# PowerSwitch_P12V.net
KiCad netlist of a schematic drawn in Altium Designer
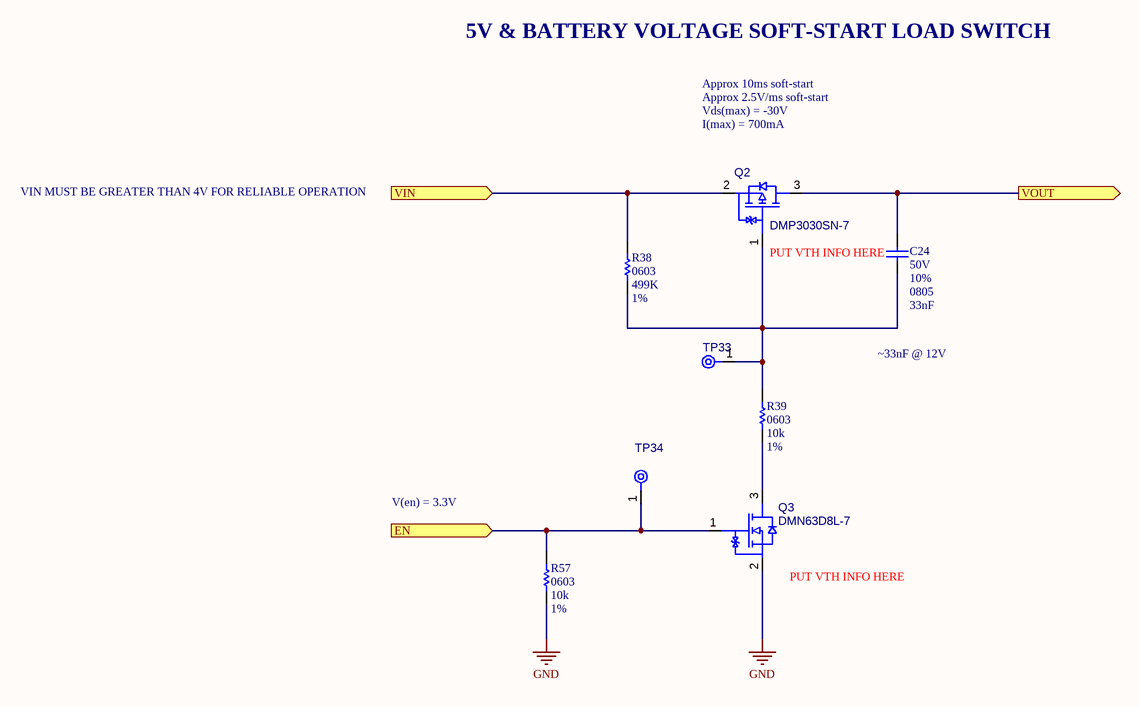
[diagram p0: PowerSwitch_P12V.SchDoc]

(export (version "E")
  (design (tool "Eeschema 10.0.6"))
  (components
    (comp (ref "C24")
      (value "33nF")
      (footprint "CAPC2013X95X50ML10T25")
      (description "Chip Capacitor, 33nF, 10%, 50 V, X7R 0805 (2012 Metric)")
      (fields
        (field (name "VOLTAGE RATING") "50V")
        (field (name "TOLERANCE") "10%")
        (field (name "CASE/PACKAGE") "0805")
        (field (name "Comment") "Capacitor 33nF 10%, 50V, X7R, 0805")
      )
      (libsource (lib "Applied Physics Lab") (part "CAP-NP-2"))
    )
    (comp (ref "Q2")
      (value "DMP3030SN-7")
      (footprint "SOT95P164X140-3M")
      (description "Trans Mosfet P-ch 30V 0.7A 3-PIN SC-59 T/r / Mosfet P-ch 30V 700MA SC59-3")
      (libsource (lib "Applied Physics Lab") (part "CMP-00006-6"))
    )
    (comp (ref "Q3")
      (value "DMN63D8L-7")
      (footprint "SOT95P240X110-3M")
      (description "Trans Mosfet N-ch 30V 0.35A 3-PIN SOT-23 T/r")
      (libsource (lib "Applied Physics Lab") (part "CMP-00005-6"))
    )
    (comp (ref "R38")
      (value "499K")
      (footprint "RESC1609X50X30ML08T20")
      (description "Chip Resistor, 499k Ohm, +/- 1%, 0.1 W, -55 to 155 degC, 0603 (1608 Metric)")
      (fields
        (field (name "POWER") "100mW")
        (field (name "CASE/PACKAGE") "0603")
        (field (name "TOLERANCE") "1%")
        (field (name "Comment") "Resistor 499K +/-1% 0603 100 mW")
      )
      (libsource (lib "Applied Physics Lab") (part "RES-2"))
    )
    (comp (ref "R39")
      (value "10k")
      (footprint "RESC1608X55X25ML10T15")
      (description "Chip Resistor, 10 KOhm, +/- 1%, 01 W, -55 to 155 degC, 0603 (1608 Metric)")
      (fields
        (field (name "POWER") "100mW")
        (field (name "CASE/PACKAGE") "0603")
        (field (name "TOLERANCE") "1%")
        (field (name "Comment") "Resistor 10k +/-1% 0603 100 mW")
      )
      (libsource (lib "Applied Physics Lab") (part "RES-2"))
    )
    (comp (ref "R57")
      (value "10k")
      (footprint "RESC1608X55X25ML10T15")
      (description "Chip Resistor, 10 KOhm, +/- 1%, 01 W, -55 to 155 degC, 0603 (1608 Metric)")
      (fields
        (field (name "POWER") "100mW")
        (field (name "CASE/PACKAGE") "0603")
        (field (name "TOLERANCE") "1%")
        (field (name "Comment") "Resistor 10k +/-1% 0603 100 mW")
      )
      (libsource (lib "Applied Physics Lab") (part "RES-2"))
    )
    (comp (ref "TP33")
      (value "TPAD6R-CIRCLED")
      (footprint "TP06R - Circled")
      (description "0.6mm round with a silkscreen circle.")
      (libsource (lib "Applied Physics Lab") (part "CMP-001-0001-4"))
    )
    (comp (ref "TP34")
      (value "TPAD6R-CIRCLED")
      (footprint "TP06R - Circled")
      (description "0.6mm round with a silkscreen circle.")
      (libsource (lib "Applied Physics Lab") (part "CMP-001-0001-4"))
    )
  )
  (nets
    (net (code "1") (name "/EN") (class "Default")
      (node (ref "Q3") (pin "1") (pinfunction "G_1") (pintype "passive"))
      (node (ref "R57") (pin "2") (pinfunction "2_2") (pintype "passive"))
      (node (ref "TP34") (pin "1") (pinfunction "TP_1") (pintype "passive"))
    )
    (net (code "2") (name "/VIN") (class "Default")
      (node (ref "Q2") (pin "2") (pinfunction "S_2") (pintype "passive"))
      (node (ref "R38") (pin "2") (pinfunction "2_2") (pintype "passive"))
    )
    (net (code "3") (name "/VOUT") (class "Default")
      (node (ref "C24") (pin "2") (pinfunction "2_2") (pintype "passive"))
      (node (ref "Q2") (pin "3") (pinfunction "D_3") (pintype "passive"))
    )
    (net (code "4") (name "GND") (class "Default")
      (node (ref "Q3") (pin "2") (pinfunction "S_2") (pintype "passive"))
      (node (ref "R57") (pin "1") (pinfunction "1_1") (pintype "passive"))
    )
    (net (code "5") (name "Net-(Q2-G)") (class "Default")
      (node (ref "C24") (pin "1") (pinfunction "1_1") (pintype "passive"))
      (node (ref "Q2") (pin "1") (pinfunction "G_1") (pintype "passive"))
      (node (ref "R38") (pin "1") (pinfunction "1_1") (pintype "passive"))
      (node (ref "R39") (pin "2") (pinfunction "2_2") (pintype "passive"))
      (node (ref "TP33") (pin "1") (pinfunction "TP_1") (pintype "passive"))
    )
    (net (code "6") (name "Net-(Q3-D)") (class "Default")
      (node (ref "Q3") (pin "3") (pinfunction "D_3") (pintype "passive"))
      (node (ref "R39") (pin "1") (pinfunction "1_1") (pintype "passive"))
    )
  )
)
